# integrator.net
KiCad netlist of a schematic drawn in Altium Designer
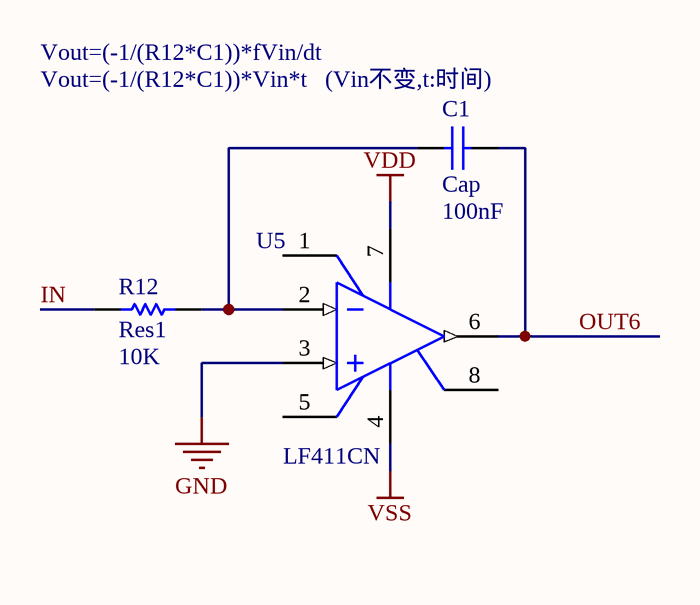
[diagram p0: integrator.SchDoc]

(export (version "E")
  (design (tool "Eeschema 10.0.6"))
  (components
    (comp (ref "C1")
      (value "Cap")
      (footprint "RAD-0.3")
      (description "Capacitor")
      (fields (field (name "ALTIUM_VALUE") "100nF") (field (name "PUBLISHER") "Altium Limited"))
      (libsource (lib "Miscellaneous Devices") (part "Cap"))
    )
    (comp (ref "R12")
      (value "Res1")
      (footprint "AXIAL-0.3")
      (description "Resistor")
      (fields (field (name "ALTIUM_VALUE") "10K") (field (name "PUBLISHER") "Altium Limited"))
      (libsource (lib "Miscellaneous Devices") (part "Res1"))
    )
    (comp (ref "U5")
      (value "LF411CN")
      (footprint "N08E")
      (description "Low Offset, Low Drift JFET Input Operational Amplifier, 8-pin MDIP")
      (fields
        (field (name "MANUFACTURER") "National Semiconductor")
        (field (name "PUBLISHER") "Altium Limited")
      )
      (libsource (lib "NSC Amplifier") (part "LF411CN"))
    )
  )
  (nets
    (net (code "1") (name "/IN") (class "Default")
      (node (ref "R12") (pin "2") (pinfunction "2_2") (pintype "passive"))
    )
    (net (code "2") (name "/OUT6") (class "Default")
      (node (ref "C1") (pin "2") (pinfunction "2_2") (pintype "passive"))
      (node (ref "U5") (pin "6") (pinfunction "OUT_6") (pintype "output"))
    )
    (net (code "3") (name "GND") (class "Default")
      (node (ref "U5") (pin "3") (pinfunction "IN+_3") (pintype "input"))
    )
    (net (code "4") (name "Net-(U5-IN-)") (class "Default")
      (node (ref "C1") (pin "1") (pinfunction "1_1") (pintype "passive"))
      (node (ref "R12") (pin "1") (pinfunction "1_1") (pintype "passive"))
      (node (ref "U5") (pin "2") (pinfunction "IN-_2") (pintype "input"))
    )
    (net (code "5") (name "VDD") (class "Default")
      (node (ref "U5") (pin "7") (pinfunction "V+_7") (pintype "power_in"))
    )
    (net (code "6") (name "VSS") (class "Default")
      (node (ref "U5") (pin "4") (pinfunction "V-_4") (pintype "power_in"))
    )
    (net (code "7") (name "unconnected-(U5-BAL-Pad1)") (class "Default")
      (node (ref "U5") (pin "1") (pinfunction "BAL_1") (pintype "passive"))
    )
    (net (code "8") (name "unconnected-(U5-BAL-Pad5)") (class "Default")
      (node (ref "U5") (pin "5") (pinfunction "BAL_5") (pintype "passive"))
    )
    (net (code "9") (name "unconnected-(U5-NC-Pad8)") (class "Default")
      (node (ref "U5") (pin "8") (pinfunction "NC_8") (pintype "passive"))
    )
  )
)
